# 3_-_Fuses.net
KiCad netlist of a schematic drawn in Altium Designer
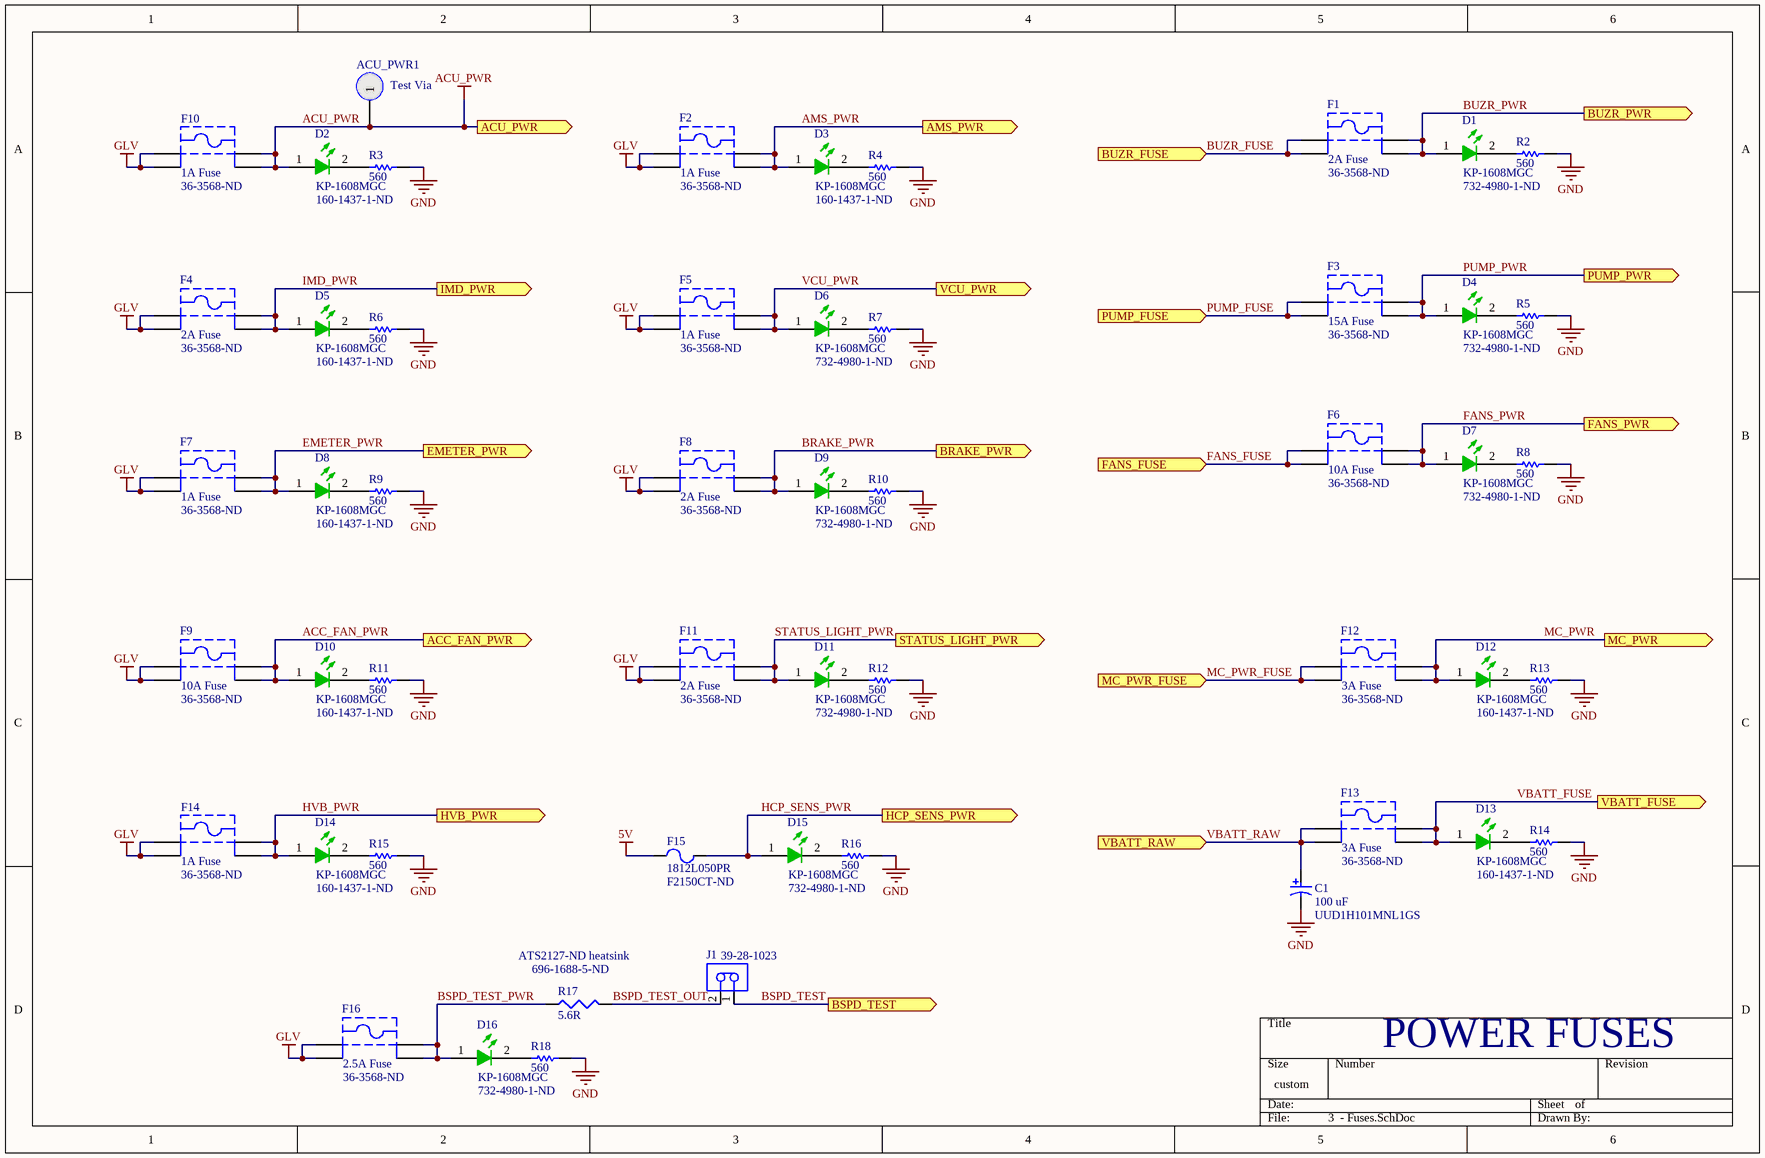
[diagram p0: 3  - Fuses.SchDoc]

(export (version "E")
  (design (tool "Eeschema 10.0.6"))
  (components
    (comp (ref "ACU_PWR1")
      (value "Test Via")
      (footprint "Test Via")
      (libsource (lib "BRAKETEMPComponents") (part "Test VIa"))
    )
    (comp (ref "C1")
      (value "UUD1H101MNL1GS")
      (footprint "NIC-CAPA2-8X10_V")
      (fields
        (field (name "MANUFACTURER") "Nichicon")
        (field (name "RATED CAPACITANCE") "100 uF")
        (field (name "TOLERANCE") "±20%")
      )
      (libsource (lib "Altium Content Vault") (part "CMP-0687-00073-1"))
    )
    (comp (ref "D1")
      (value "KP-1608MGC")
      (footprint "KING-0603LED_GREEN_V")
      (description "LED, SMT, 0603(1608), 1.1mm thickness, Green")
      (fields
        (field (name "MANUFACTURER") "Kingbright")
        (field (name "SUPPLIER PART NUMBER 1") "732-4980-1-ND")
      )
      (libsource (lib "Altium Content Vault") (part "KING-LED-GREEN-A1K2-2"))
    )
    (comp (ref "D2")
      (value "KP-1608MGC")
      (footprint "KING-0603LED_GREEN_V")
      (description "LED, SMT, 0603(1608), 1.1mm thickness, Green")
      (fields
        (field (name "MANUFACTURER") "Kingbright")
        (field (name "SUPPLIER PART NUMBER 1") "160-1437-1-ND")
      )
      (libsource (lib "Altium Content Vault") (part "KING-LED-GREEN-A1K2-2"))
    )
    (comp (ref "D3")
      (value "KP-1608MGC")
      (footprint "KING-0603LED_GREEN_V")
      (description "LED, SMT, 0603(1608), 1.1mm thickness, Green")
      (fields
        (field (name "MANUFACTURER") "Kingbright")
        (field (name "SUPPLIER PART NUMBER 1") "160-1437-1-ND")
      )
      (libsource (lib "Altium Content Vault") (part "KING-LED-GREEN-A1K2-2"))
    )
    (comp (ref "D4")
      (value "KP-1608MGC")
      (footprint "KING-0603LED_GREEN_V")
      (description "LED, SMT, 0603(1608), 1.1mm thickness, Green")
      (fields
        (field (name "MANUFACTURER") "Kingbright")
        (field (name "SUPPLIER PART NUMBER 1") "732-4980-1-ND")
      )
      (libsource (lib "Altium Content Vault") (part "KING-LED-GREEN-A1K2-2"))
    )
    (comp (ref "D5")
      (value "KP-1608MGC")
      (footprint "KING-0603LED_GREEN_V")
      (description "LED, SMT, 0603(1608), 1.1mm thickness, Green")
      (fields
        (field (name "MANUFACTURER") "Kingbright")
        (field (name "SUPPLIER PART NUMBER 1") "160-1437-1-ND")
      )
      (libsource (lib "Altium Content Vault") (part "KING-LED-GREEN-A1K2-2"))
    )
    (comp (ref "D6")
      (value "KP-1608MGC")
      (footprint "KING-0603LED_GREEN_V")
      (description "LED, SMT, 0603(1608), 1.1mm thickness, Green")
      (fields
        (field (name "MANUFACTURER") "Kingbright")
        (field (name "SUPPLIER PART NUMBER 1") "732-4980-1-ND")
      )
      (libsource (lib "Altium Content Vault") (part "KING-LED-GREEN-A1K2-2"))
    )
    (comp (ref "D7")
      (value "KP-1608MGC")
      (footprint "KING-0603LED_GREEN_V")
      (description "LED, SMT, 0603(1608), 1.1mm thickness, Green")
      (fields
        (field (name "MANUFACTURER") "Kingbright")
        (field (name "SUPPLIER PART NUMBER 1") "732-4980-1-ND")
      )
      (libsource (lib "Altium Content Vault") (part "KING-LED-GREEN-A1K2-2"))
    )
    (comp (ref "D8")
      (value "KP-1608MGC")
      (footprint "KING-0603LED_GREEN_V")
      (description "LED, SMT, 0603(1608), 1.1mm thickness, Green")
      (fields
        (field (name "MANUFACTURER") "Kingbright")
        (field (name "SUPPLIER PART NUMBER 1") "160-1437-1-ND")
      )
      (libsource (lib "Altium Content Vault") (part "KING-LED-GREEN-A1K2-2"))
    )
    (comp (ref "D9")
      (value "KP-1608MGC")
      (footprint "KING-0603LED_GREEN_V")
      (description "LED, SMT, 0603(1608), 1.1mm thickness, Green")
      (fields
        (field (name "MANUFACTURER") "Kingbright")
        (field (name "SUPPLIER PART NUMBER 1") "732-4980-1-ND")
      )
      (libsource (lib "Altium Content Vault") (part "KING-LED-GREEN-A1K2-2"))
    )
    (comp (ref "D10")
      (value "KP-1608MGC")
      (footprint "KING-0603LED_GREEN_V")
      (description "LED, SMT, 0603(1608), 1.1mm thickness, Green")
      (fields
        (field (name "MANUFACTURER") "Kingbright")
        (field (name "SUPPLIER PART NUMBER 1") "160-1437-1-ND")
      )
      (libsource (lib "Altium Content Vault") (part "KING-LED-GREEN-A1K2-2"))
    )
    (comp (ref "D11")
      (value "KP-1608MGC")
      (footprint "KING-0603LED_GREEN_V")
      (description "LED, SMT, 0603(1608), 1.1mm thickness, Green")
      (fields
        (field (name "MANUFACTURER") "Kingbright")
        (field (name "SUPPLIER PART NUMBER 1") "732-4980-1-ND")
      )
      (libsource (lib "Altium Content Vault") (part "KING-LED-GREEN-A1K2-2"))
    )
    (comp (ref "D12")
      (value "KP-1608MGC")
      (footprint "KING-0603LED_GREEN_V")
      (description "LED, SMT, 0603(1608), 1.1mm thickness, Green")
      (fields
        (field (name "MANUFACTURER") "Kingbright")
        (field (name "SUPPLIER PART NUMBER 1") "160-1437-1-ND")
      )
      (libsource (lib "Altium Content Vault") (part "KING-LED-GREEN-A1K2-2"))
    )
    (comp (ref "D13")
      (value "KP-1608MGC")
      (footprint "KING-0603LED_GREEN_V")
      (description "LED, SMT, 0603(1608), 1.1mm thickness, Green")
      (fields
        (field (name "MANUFACTURER") "Kingbright")
        (field (name "SUPPLIER PART NUMBER 1") "160-1437-1-ND")
      )
      (libsource (lib "Altium Content Vault") (part "KING-LED-GREEN-A1K2-2"))
    )
    (comp (ref "D14")
      (value "KP-1608MGC")
      (footprint "KING-0603LED_GREEN_V")
      (description "LED, SMT, 0603(1608), 1.1mm thickness, Green")
      (fields
        (field (name "MANUFACTURER") "Kingbright")
        (field (name "SUPPLIER PART NUMBER 1") "160-1437-1-ND")
      )
      (libsource (lib "Altium Content Vault") (part "KING-LED-GREEN-A1K2-2"))
    )
    (comp (ref "D15")
      (value "KP-1608MGC")
      (footprint "KING-0603LED_GREEN_V")
      (description "LED, SMT, 0603(1608), 1.1mm thickness, Green")
      (fields
        (field (name "MANUFACTURER") "Kingbright")
        (field (name "SUPPLIER PART NUMBER 1") "732-4980-1-ND")
      )
      (libsource (lib "Altium Content Vault") (part "KING-LED-GREEN-A1K2-2"))
    )
    (comp (ref "D16")
      (value "KP-1608MGC")
      (footprint "KING-0603LED_GREEN_V")
      (description "LED, SMT, 0603(1608), 1.1mm thickness, Green")
      (fields
        (field (name "MANUFACTURER") "Kingbright")
        (field (name "SUPPLIER PART NUMBER 1") "732-4980-1-ND")
      )
      (libsource (lib "Altium Content Vault") (part "KING-LED-GREEN-A1K2-2"))
    )
    (comp (ref "F1")
      (value "36-3568-ND")
      (footprint "KSTN-3568_V")
      (description "Fuse Holder, 20 A, 500 V, -50 to 145 degC, 4-Pin THD, RoHS")
      (fields (field (name "MANUFACTURER") "Keystone"))
      (libsource (lib "Altium Content Vault") (part "FUSE_HOLDER-4"))
    )
    (comp (ref "F2")
      (value "36-3568-ND")
      (footprint "KSTN-3568_V")
      (description "Fuse Holder, 20 A, 500 V, -50 to 145 degC, 4-Pin THD, RoHS")
      (fields (field (name "MANUFACTURER") "Keystone"))
      (libsource (lib "Altium Content Vault") (part "FUSE_HOLDER-4"))
    )
    (comp (ref "F3")
      (value "36-3568-ND")
      (footprint "KSTN-3568_V")
      (description "Fuse Holder, 20 A, 500 V, -50 to 145 degC, 4-Pin THD, RoHS")
      (fields (field (name "MANUFACTURER") "Keystone"))
      (libsource (lib "Altium Content Vault") (part "FUSE_HOLDER-4"))
    )
    (comp (ref "F4")
      (value "36-3568-ND")
      (footprint "KSTN-3568_V")
      (description "Fuse Holder, 20 A, 500 V, -50 to 145 degC, 4-Pin THD, RoHS")
      (fields (field (name "MANUFACTURER") "Keystone"))
      (libsource (lib "Altium Content Vault") (part "FUSE_HOLDER-4"))
    )
    (comp (ref "F5")
      (value "36-3568-ND")
      (footprint "KSTN-3568_V")
      (description "Fuse Holder, 20 A, 500 V, -50 to 145 degC, 4-Pin THD, RoHS")
      (fields (field (name "MANUFACTURER") "Keystone"))
      (libsource (lib "Altium Content Vault") (part "FUSE_HOLDER-4"))
    )
    (comp (ref "F6")
      (value "36-3568-ND")
      (footprint "KSTN-3568_V")
      (fields (field (name "MANUFACTURER") "Keystone"))
      (libsource (lib "Altium Content Vault") (part "FUSE_HOLDER-4"))
    )
    (comp (ref "F7")
      (value "36-3568-ND")
      (footprint "KSTN-3568_V")
      (description "Fuse Holder, 20 A, 500 V, -50 to 145 degC, 4-Pin THD, RoHS")
      (fields (field (name "MANUFACTURER") "Keystone"))
      (libsource (lib "Altium Content Vault") (part "FUSE_HOLDER-4"))
    )
    (comp (ref "F8")
      (value "36-3568-ND")
      (footprint "KSTN-3568_V")
      (description "Fuse Holder, 20 A, 500 V, -50 to 145 degC, 4-Pin THD, RoHS")
      (fields (field (name "MANUFACTURER") "Keystone"))
      (libsource (lib "Altium Content Vault") (part "FUSE_HOLDER-4"))
    )
    (comp (ref "F9")
      (value "36-3568-ND")
      (footprint "KSTN-3568_V")
      (description "Fuse Holder, 20 A, 500 V, -50 to 145 degC, 4-Pin THD, RoHS")
      (fields (field (name "MANUFACTURER") "Keystone"))
      (libsource (lib "Altium Content Vault") (part "FUSE_HOLDER-4"))
    )
    (comp (ref "F10")
      (value "36-3568-ND")
      (footprint "KSTN-3568_V")
      (description "Fuse Holder, 20 A, 500 V, -50 to 145 degC, 4-Pin THD, RoHS")
      (fields (field (name "MANUFACTURER") "Keystone"))
      (libsource (lib "Altium Content Vault") (part "FUSE_HOLDER-4"))
    )
    (comp (ref "F11")
      (value "36-3568-ND")
      (footprint "KSTN-3568_V")
      (description "Fuse Holder, 20 A, 500 V, -50 to 145 degC, 4-Pin THD, RoHS")
      (fields (field (name "MANUFACTURER") "Keystone"))
      (libsource (lib "Altium Content Vault") (part "FUSE_HOLDER-4"))
    )
    (comp (ref "F12")
      (value "36-3568-ND")
      (footprint "KSTN-3568_V")
      (description "Fuse Holder, 20 A, 500 V, -50 to 145 degC, 4-Pin THD, RoHS")
      (fields (field (name "MANUFACTURER") "Keystone"))
      (libsource (lib "Altium Content Vault") (part "FUSE_HOLDER-4"))
    )
    (comp (ref "F13")
      (value "36-3568-ND")
      (footprint "KSTN-3568_V")
      (description "Fuse Holder, 20 A, 500 V, -50 to 145 degC, 4-Pin THD, RoHS")
      (fields (field (name "MANUFACTURER") "Keystone"))
      (libsource (lib "Altium Content Vault") (part "FUSE_HOLDER-4"))
    )
    (comp (ref "F14")
      (value "36-3568-ND")
      (footprint "KSTN-3568_V")
      (description "Fuse Holder, 20 A, 500 V, -50 to 145 degC, 4-Pin THD, RoHS")
      (fields (field (name "MANUFACTURER") "Keystone"))
      (libsource (lib "Altium Content Vault") (part "FUSE_HOLDER-4"))
    )
    (comp (ref "F15")
      (value "1812L050PR")
      (footprint "LFUS-1812L050_V")
      (fields (field (name "TOLERANCE") "1%") (field (name "SUPPLIER PART NUMBER 1") "F2150CT-ND"))
      (libsource (lib "Power_PCB") (part "CMP-1700-00002-1"))
    )
    (comp (ref "F16")
      (value "36-3568-ND")
      (footprint "KSTN-3568_V")
      (description "Fuse Holder, 20 A, 500 V, -50 to 145 degC, 4-Pin THD, RoHS")
      (fields (field (name "MANUFACTURER") "Keystone"))
      (libsource (lib "Altium Content Vault") (part "FUSE_HOLDER-4"))
    )
    (comp (ref "J1")
      (value "39-28-1023")
      (footprint "MOLX-39-28-1023-2_V")
      (fields (field (name "MANUFACTURER") "Molex"))
      (libsource (lib "Altium Content Vault") (part "CN-2P-F-QF2"))
    )
    (comp (ref "R2")
      (value "560")
      (footprint "RESC0603(1608)_L")
      (description "0603 (1608 Metric) Chip Resistor")
      (libsource (lib "Altium Content Vault") (part "RES_3"))
    )
    (comp (ref "R3")
      (value "560")
      (footprint "RESC0603(1608)_L")
      (description "0603 (1608 Metric) Chip Resistor")
      (libsource (lib "Altium Content Vault") (part "RES_3"))
    )
    (comp (ref "R4")
      (value "560")
      (footprint "RESC0603(1608)_L")
      (description "0603 (1608 Metric) Chip Resistor")
      (libsource (lib "Altium Content Vault") (part "RES_3"))
    )
    (comp (ref "R5")
      (value "560")
      (footprint "RESC0603(1608)_L")
      (description "0603 (1608 Metric) Chip Resistor")
      (libsource (lib "Altium Content Vault") (part "RES_3"))
    )
    (comp (ref "R6")
      (value "560")
      (footprint "RESC0603(1608)_L")
      (description "0603 (1608 Metric) Chip Resistor")
      (libsource (lib "Altium Content Vault") (part "RES_3"))
    )
    (comp (ref "R7")
      (value "560")
      (footprint "RESC0603(1608)_L")
      (description "0603 (1608 Metric) Chip Resistor")
      (libsource (lib "Altium Content Vault") (part "RES_3"))
    )
    (comp (ref "R8")
      (value "560")
      (footprint "RESC0603(1608)_L")
      (description "0603 (1608 Metric) Chip Resistor")
      (libsource (lib "Altium Content Vault") (part "RES_3"))
    )
    (comp (ref "R9")
      (value "560")
      (footprint "RESC0603(1608)_L")
      (description "0603 (1608 Metric) Chip Resistor")
      (libsource (lib "Altium Content Vault") (part "RES_3"))
    )
    (comp (ref "R10")
      (value "560")
      (footprint "RESC0603(1608)_L")
      (description "0603 (1608 Metric) Chip Resistor")
      (libsource (lib "Altium Content Vault") (part "RES_3"))
    )
    (comp (ref "R11")
      (value "560")
      (footprint "RESC0603(1608)_L")
      (description "0603 (1608 Metric) Chip Resistor")
      (libsource (lib "Altium Content Vault") (part "RES_3"))
    )
    (comp (ref "R12")
      (value "560")
      (footprint "RESC0603(1608)_L")
      (description "0603 (1608 Metric) Chip Resistor")
      (libsource (lib "Altium Content Vault") (part "RES_3"))
    )
    (comp (ref "R13")
      (value "560")
      (footprint "RESC0603(1608)_L")
      (description "0603 (1608 Metric) Chip Resistor")
      (libsource (lib "Altium Content Vault") (part "RES_3"))
    )
    (comp (ref "R14")
      (value "560")
      (footprint "RESC0603(1608)_L")
      (description "0603 (1608 Metric) Chip Resistor")
      (libsource (lib "Altium Content Vault") (part "RES_3"))
    )
    (comp (ref "R15")
      (value "560")
      (footprint "RESC0603(1608)_L")
      (description "0603 (1608 Metric) Chip Resistor")
      (libsource (lib "Altium Content Vault") (part "RES_3"))
    )
    (comp (ref "R16")
      (value "560")
      (footprint "RESC0603(1608)_L")
      (description "0603 (1608 Metric) Chip Resistor")
      (libsource (lib "Altium Content Vault") (part "RES_3"))
    )
    (comp (ref "R17")
      (value "5.6R")
      (footprint "TO220AC")
      (description "Resistor")
      (fields
        (field (name "SUPPLIER PART NUMBER 1") "696-1688-5-ND")
        (field (name "PUBLISHER") "Altium Limited")
      )
      (libsource (lib "Miscellaneous Devices") (part "Res3"))
    )
    (comp (ref "R18")
      (value "560")
      (footprint "RESC0603(1608)_L")
      (description "0603 (1608 Metric) Chip Resistor")
      (libsource (lib "Altium Content Vault") (part "RES_3"))
    )
  )
  (nets
    (net (code "1") (name "/ACC_FAN_PWR") (class "Default")
      (node (ref "D10") (pin "1") (pinfunction "A_1") (pintype "passive"))
      (node (ref "F9") (pin "3") (pinfunction "3_3") (pintype "passive"))
      (node (ref "F9") (pin "4") (pinfunction "4_4") (pintype "passive"))
    )
    (net (code "2") (name "/AMS_PWR") (class "Default")
      (node (ref "D3") (pin "1") (pinfunction "A_1") (pintype "passive"))
      (node (ref "F2") (pin "3") (pinfunction "3_3") (pintype "passive"))
      (node (ref "F2") (pin "4") (pinfunction "4_4") (pintype "passive"))
    )
    (net (code "3") (name "/BRAKE_PWR") (class "Default")
      (node (ref "D9") (pin "1") (pinfunction "A_1") (pintype "passive"))
      (node (ref "F8") (pin "3") (pinfunction "3_3") (pintype "passive"))
      (node (ref "F8") (pin "4") (pinfunction "4_4") (pintype "passive"))
    )
    (net (code "4") (name "/BSPD_TEST") (class "Default")
      (node (ref "J1") (pin "1") (pinfunction "1_1") (pintype "passive"))
    )
    (net (code "5") (name "/BSPD_TEST_OUT") (class "Default")
      (node (ref "J1") (pin "2") (pinfunction "2_2") (pintype "passive"))
      (node (ref "R17") (pin "2") (pinfunction "2_2") (pintype "passive"))
    )
    (net (code "6") (name "/BSPD_TEST_PWR") (class "Default")
      (node (ref "D16") (pin "1") (pinfunction "A_1") (pintype "passive"))
      (node (ref "F16") (pin "3") (pinfunction "3_3") (pintype "passive"))
      (node (ref "F16") (pin "4") (pinfunction "4_4") (pintype "passive"))
      (node (ref "R17") (pin "1") (pinfunction "1_1") (pintype "passive"))
    )
    (net (code "7") (name "/BUZR_FUSE") (class "Default")
      (node (ref "F1") (pin "1") (pinfunction "1_1") (pintype "passive"))
      (node (ref "F1") (pin "2") (pinfunction "2_2") (pintype "passive"))
    )
    (net (code "8") (name "/BUZR_PWR") (class "Default")
      (node (ref "D1") (pin "1") (pinfunction "A_1") (pintype "passive"))
      (node (ref "F1") (pin "3") (pinfunction "3_3") (pintype "passive"))
      (node (ref "F1") (pin "4") (pinfunction "4_4") (pintype "passive"))
    )
    (net (code "9") (name "/EMETER_PWR") (class "Default")
      (node (ref "D8") (pin "1") (pinfunction "A_1") (pintype "passive"))
      (node (ref "F7") (pin "3") (pinfunction "3_3") (pintype "passive"))
      (node (ref "F7") (pin "4") (pinfunction "4_4") (pintype "passive"))
    )
    (net (code "10") (name "/FANS_FUSE") (class "Default")
      (node (ref "F6") (pin "1") (pinfunction "1_1") (pintype "passive"))
      (node (ref "F6") (pin "2") (pinfunction "2_2") (pintype "passive"))
    )
    (net (code "11") (name "/FANS_PWR") (class "Default")
      (node (ref "D7") (pin "1") (pinfunction "A_1") (pintype "passive"))
      (node (ref "F6") (pin "3") (pinfunction "3_3") (pintype "passive"))
      (node (ref "F6") (pin "4") (pinfunction "4_4") (pintype "passive"))
    )
    (net (code "12") (name "/HCP_SENS_PWR") (class "Default")
      (node (ref "D15") (pin "1") (pinfunction "A_1") (pintype "passive"))
      (node (ref "F15") (pin "2") (pinfunction "2_2") (pintype "passive"))
    )
    (net (code "13") (name "/HVB_PWR") (class "Default")
      (node (ref "D14") (pin "1") (pinfunction "A_1") (pintype "passive"))
      (node (ref "F14") (pin "3") (pinfunction "3_3") (pintype "passive"))
      (node (ref "F14") (pin "4") (pinfunction "4_4") (pintype "passive"))
    )
    (net (code "14") (name "/IMD_PWR") (class "Default")
      (node (ref "D5") (pin "1") (pinfunction "A_1") (pintype "passive"))
      (node (ref "F4") (pin "3") (pinfunction "3_3") (pintype "passive"))
      (node (ref "F4") (pin "4") (pinfunction "4_4") (pintype "passive"))
    )
    (net (code "15") (name "/MC_PWR") (class "Default")
      (node (ref "D12") (pin "1") (pinfunction "A_1") (pintype "passive"))
      (node (ref "F12") (pin "3") (pinfunction "3_3") (pintype "passive"))
      (node (ref "F12") (pin "4") (pinfunction "4_4") (pintype "passive"))
    )
    (net (code "16") (name "/MC_PWR_FUSE") (class "Default")
      (node (ref "F12") (pin "1") (pinfunction "1_1") (pintype "passive"))
      (node (ref "F12") (pin "2") (pinfunction "2_2") (pintype "passive"))
    )
    (net (code "17") (name "/PUMP_FUSE") (class "Default")
      (node (ref "F3") (pin "1") (pinfunction "1_1") (pintype "passive"))
      (node (ref "F3") (pin "2") (pinfunction "2_2") (pintype "passive"))
    )
    (net (code "18") (name "/PUMP_PWR") (class "Default")
      (node (ref "D4") (pin "1") (pinfunction "A_1") (pintype "passive"))
      (node (ref "F3") (pin "3") (pinfunction "3_3") (pintype "passive"))
      (node (ref "F3") (pin "4") (pinfunction "4_4") (pintype "passive"))
    )
    (net (code "19") (name "/STATUS_LIGHT_PWR") (class "Default")
      (node (ref "D11") (pin "1") (pinfunction "A_1") (pintype "passive"))
      (node (ref "F11") (pin "3") (pinfunction "3_3") (pintype "passive"))
      (node (ref "F11") (pin "4") (pinfunction "4_4") (pintype "passive"))
    )
    (net (code "20") (name "/VBATT_FUSE") (class "Default")
      (node (ref "D13") (pin "1") (pinfunction "A_1") (pintype "passive"))
      (node (ref "F13") (pin "3") (pinfunction "3_3") (pintype "passive"))
      (node (ref "F13") (pin "4") (pinfunction "4_4") (pintype "passive"))
    )
    (net (code "21") (name "/VBATT_RAW") (class "Default")
      (node (ref "C1") (pin "1") (pinfunction "1_1") (pintype "passive"))
      (node (ref "F13") (pin "1") (pinfunction "1_1") (pintype "passive"))
      (node (ref "F13") (pin "2") (pinfunction "2_2") (pintype "passive"))
    )
    (net (code "22") (name "/VCU_PWR") (class "Default")
      (node (ref "D6") (pin "1") (pinfunction "A_1") (pintype "passive"))
      (node (ref "F5") (pin "3") (pinfunction "3_3") (pintype "passive"))
      (node (ref "F5") (pin "4") (pinfunction "4_4") (pintype "passive"))
    )
    (net (code "23") (name "5V") (class "Default")
      (node (ref "F15") (pin "1") (pinfunction "1_1") (pintype "passive"))
    )
    (net (code "24") (name "ACU_PWR") (class "Default")
      (node (ref "ACU_PWR1") (pin "1") (pinfunction "1_1") (pintype "passive"))
      (node (ref "D2") (pin "1") (pinfunction "A_1") (pintype "passive"))
      (node (ref "F10") (pin "3") (pinfunction "3_3") (pintype "passive"))
      (node (ref "F10") (pin "4") (pinfunction "4_4") (pintype "passive"))
    )
    (net (code "25") (name "GLV") (class "Default")
      (node (ref "F10") (pin "1") (pinfunction "1_1") (pintype "passive"))
      (node (ref "F10") (pin "2") (pinfunction "2_2") (pintype "passive"))
      (node (ref "F11") (pin "1") (pinfunction "1_1") (pintype "passive"))
      (node (ref "F11") (pin "2") (pinfunction "2_2") (pintype "passive"))
      (node (ref "F14") (pin "1") (pinfunction "1_1") (pintype "passive"))
      (node (ref "F14") (pin "2") (pinfunction "2_2") (pintype "passive"))
      (node (ref "F16") (pin "1") (pinfunction "1_1") (pintype "passive"))
      (node (ref "F16") (pin "2") (pinfunction "2_2") (pintype "passive"))
      (node (ref "F2") (pin "1") (pinfunction "1_1") (pintype "passive"))
      (node (ref "F2") (pin "2") (pinfunction "2_2") (pintype "passive"))
      (node (ref "F4") (pin "1") (pinfunction "1_1") (pintype "passive"))
      (node (ref "F4") (pin "2") (pinfunction "2_2") (pintype "passive"))
      (node (ref "F5") (pin "1") (pinfunction "1_1") (pintype "passive"))
      (node (ref "F5") (pin "2") (pinfunction "2_2") (pintype "passive"))
      (node (ref "F7") (pin "1") (pinfunction "1_1") (pintype "passive"))
      (node (ref "F7") (pin "2") (pinfunction "2_2") (pintype "passive"))
      (node (ref "F8") (pin "1") (pinfunction "1_1") (pintype "passive"))
      (node (ref "F8") (pin "2") (pinfunction "2_2") (pintype "passive"))
      (node (ref "F9") (pin "1") (pinfunction "1_1") (pintype "passive"))
      (node (ref "F9") (pin "2") (pinfunction "2_2") (pintype "passive"))
    )
    (net (code "26") (name "GND") (class "Default")
      (node (ref "C1") (pin "2") (pinfunction "2_2") (pintype "passive"))
      (node (ref "R10") (pin "2") (pinfunction "2_2") (pintype "passive"))
      (node (ref "R11") (pin "2") (pinfunction "2_2") (pintype "passive"))
      (node (ref "R12") (pin "2") (pinfunction "2_2") (pintype "passive"))
      (node (ref "R13") (pin "2") (pinfunction "2_2") (pintype "passive"))
      (node (ref "R14") (pin "2") (pinfunction "2_2") (pintype "passive"))
      (node (ref "R15") (pin "2") (pinfunction "2_2") (pintype "passive"))
      (node (ref "R16") (pin "2") (pinfunction "2_2") (pintype "passive"))
      (node (ref "R18") (pin "2") (pinfunction "2_2") (pintype "passive"))
      (node (ref "R2") (pin "2") (pinfunction "2_2") (pintype "passive"))
      (node (ref "R3") (pin "2") (pinfunction "2_2") (pintype "passive"))
      (node (ref "R4") (pin "2") (pinfunction "2_2") (pintype "passive"))
      (node (ref "R5") (pin "2") (pinfunction "2_2") (pintype "passive"))
      (node (ref "R6") (pin "2") (pinfunction "2_2") (pintype "passive"))
      (node (ref "R7") (pin "2") (pinfunction "2_2") (pintype "passive"))
      (node (ref "R8") (pin "2") (pinfunction "2_2") (pintype "passive"))
      (node (ref "R9") (pin "2") (pinfunction "2_2") (pintype "passive"))
    )
    (net (code "27") (name "Net-(D1-K)") (class "Default")
      (node (ref "D1") (pin "2") (pinfunction "K_2") (pintype "passive"))
      (node (ref "R2") (pin "1") (pinfunction "1_1") (pintype "passive"))
    )
    (net (code "28") (name "Net-(D2-K)") (class "Default")
      (node (ref "D2") (pin "2") (pinfunction "K_2") (pintype "passive"))
      (node (ref "R3") (pin "1") (pinfunction "1_1") (pintype "passive"))
    )
    (net (code "29") (name "Net-(D3-K)") (class "Default")
      (node (ref "D3") (pin "2") (pinfunction "K_2") (pintype "passive"))
      (node (ref "R4") (pin "1") (pinfunction "1_1") (pintype "passive"))
    )
    (net (code "30") (name "Net-(D4-K)") (class "Default")
      (node (ref "D4") (pin "2") (pinfunction "K_2") (pintype "passive"))
      (node (ref "R5") (pin "1") (pinfunction "1_1") (pintype "passive"))
    )
    (net (code "31") (name "Net-(D5-K)") (class "Default")
      (node (ref "D5") (pin "2") (pinfunction "K_2") (pintype "passive"))
      (node (ref "R6") (pin "1") (pinfunction "1_1") (pintype "passive"))
    )
    (net (code "32") (name "Net-(D6-K)") (class "Default")
      (node (ref "D6") (pin "2") (pinfunction "K_2") (pintype "passive"))
      (node (ref "R7") (pin "1") (pinfunction "1_1") (pintype "passive"))
    )
    (net (code "33") (name "Net-(D7-K)") (class "Default")
      (node (ref "D7") (pin "2") (pinfunction "K_2") (pintype "passive"))
      (node (ref "R8") (pin "1") (pinfunction "1_1") (pintype "passive"))
    )
    (net (code "34") (name "Net-(D8-K)") (class "Default")
      (node (ref "D8") (pin "2") (pinfunction "K_2") (pintype "passive"))
      (node (ref "R9") (pin "1") (pinfunction "1_1") (pintype "passive"))
    )
    (net (code "35") (name "Net-(D9-K)") (class "Default")
      (node (ref "D9") (pin "2") (pinfunction "K_2") (pintype "passive"))
      (node (ref "R10") (pin "1") (pinfunction "1_1") (pintype "passive"))
    )
    (net (code "36") (name "Net-(D10-K)") (class "Default")
      (node (ref "D10") (pin "2") (pinfunction "K_2") (pintype "passive"))
      (node (ref "R11") (pin "1") (pinfunction "1_1") (pintype "passive"))
    )
    (net (code "37") (name "Net-(D11-K)") (class "Default")
      (node (ref "D11") (pin "2") (pinfunction "K_2") (pintype "passive"))
      (node (ref "R12") (pin "1") (pinfunction "1_1") (pintype "passive"))
    )
    (net (code "38") (name "Net-(D12-K)") (class "Default")
      (node (ref "D12") (pin "2") (pinfunction "K_2") (pintype "passive"))
      (node (ref "R13") (pin "1") (pinfunction "1_1") (pintype "passive"))
    )
    (net (code "39") (name "Net-(D13-K)") (class "Default")
      (node (ref "D13") (pin "2") (pinfunction "K_2") (pintype "passive"))
      (node (ref "R14") (pin "1") (pinfunction "1_1") (pintype "passive"))
    )
    (net (code "40") (name "Net-(D14-K)") (class "Default")
      (node (ref "D14") (pin "2") (pinfunction "K_2") (pintype "passive"))
      (node (ref "R15") (pin "1") (pinfunction "1_1") (pintype "passive"))
    )
    (net (code "41") (name "Net-(D15-K)") (class "Default")
      (node (ref "D15") (pin "2") (pinfunction "K_2") (pintype "passive"))
      (node (ref "R16") (pin "1") (pinfunction "1_1") (pintype "passive"))
    )
    (net (code "42") (name "Net-(D16-K)") (class "Default")
      (node (ref "D16") (pin "2") (pinfunction "K_2") (pintype "passive"))
      (node (ref "R18") (pin "1") (pinfunction "1_1") (pintype "passive"))
    )
  )
)
